# DPS_PWM-00.net
KiCad netlist of a schematic drawn in EAGLE
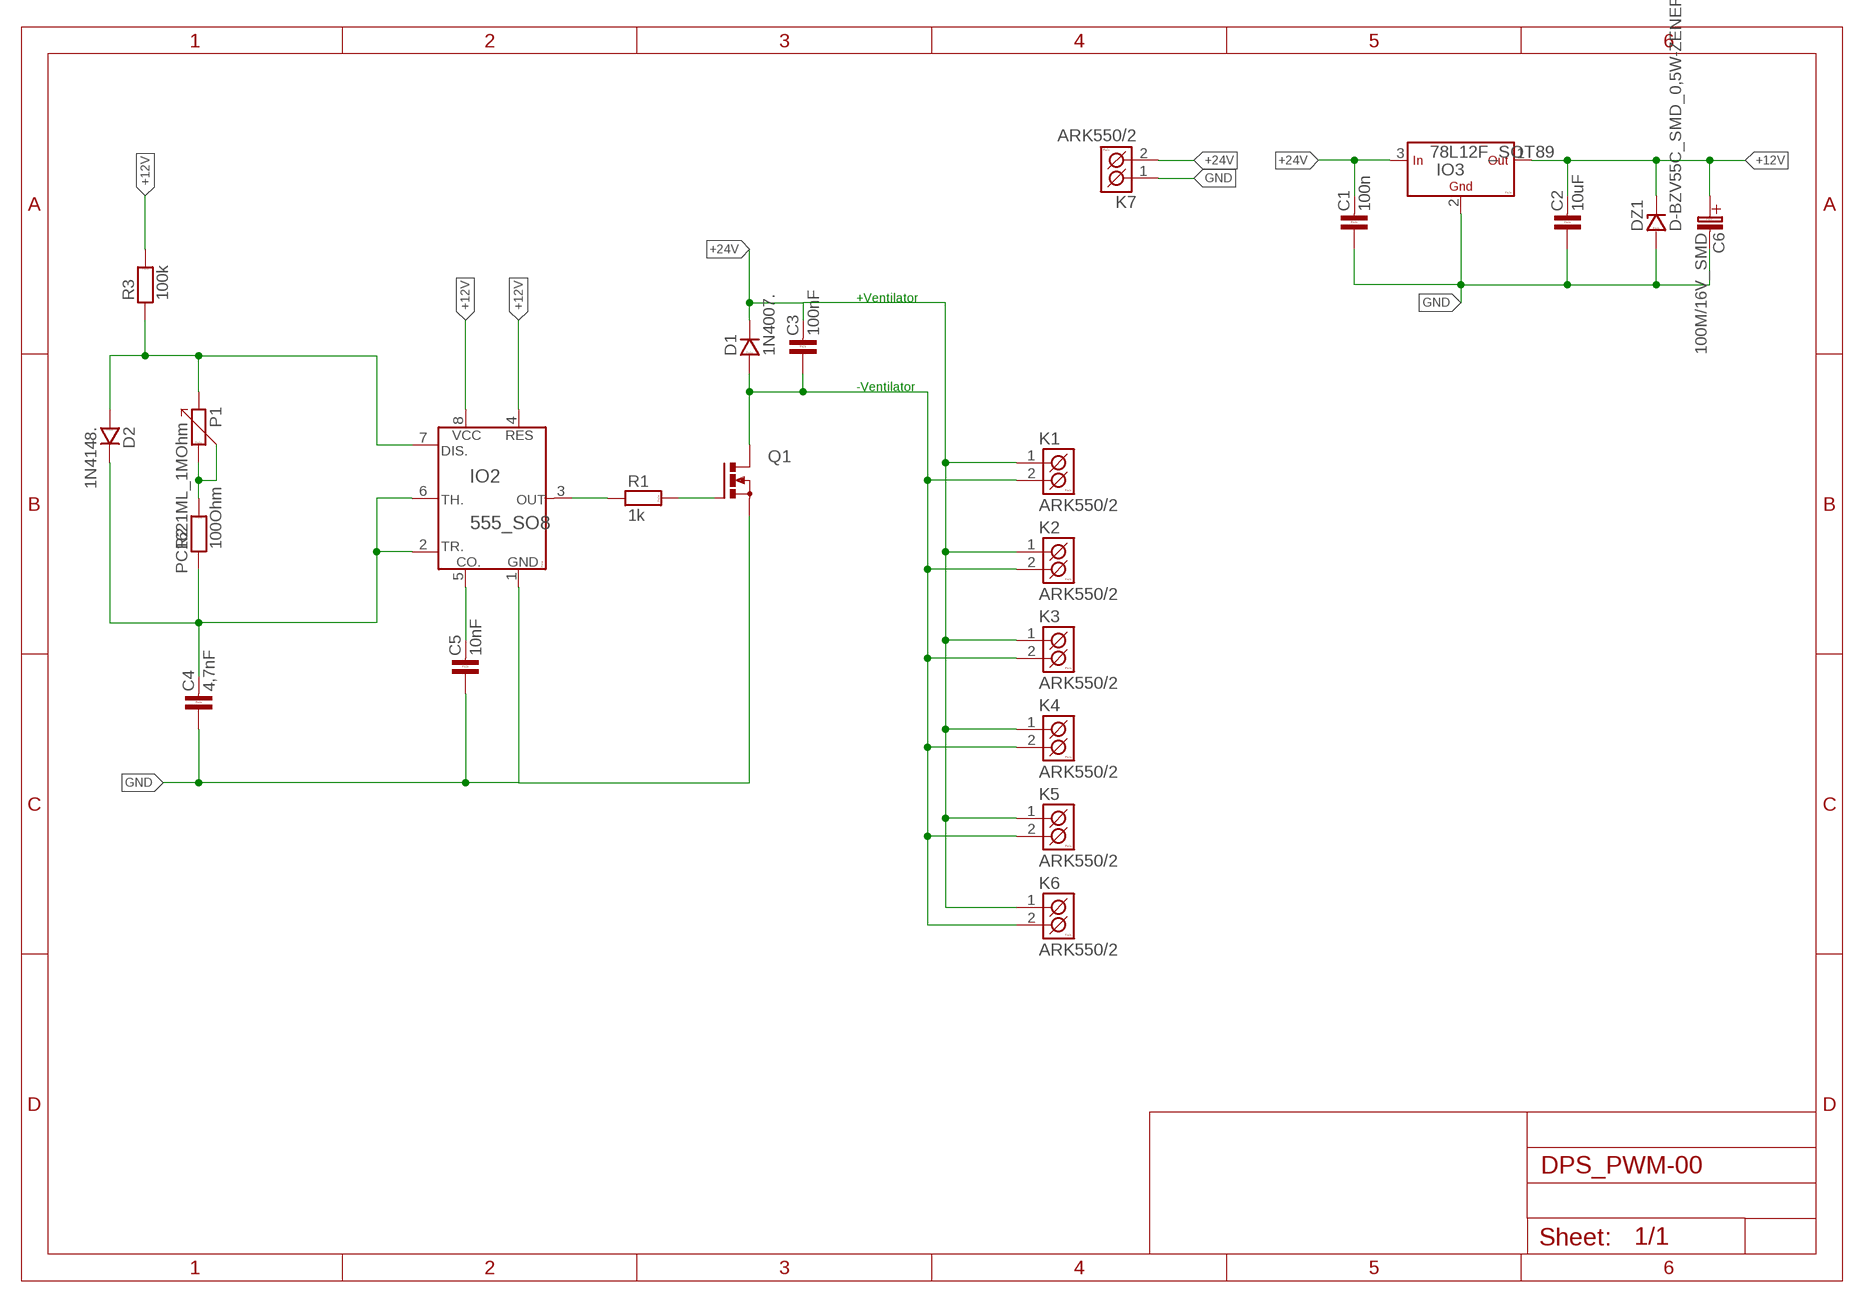
[diagram p0: schematic, sheet 1]

(export (version "E")
  (design (tool "Eeschema 10.0.6"))
  (components
    (comp (ref "C1")
      (value "100n")
      (footprint "eagle-import:1206")
      (libsource (lib "eagle-import") (part "C-KER_1206"))
    )
    (comp (ref "C2")
      (value "10uF")
      (footprint "eagle-import:1206")
      (libsource (lib "eagle-import") (part "C-KER_1206"))
    )
    (comp (ref "C3")
      (value "100nF")
      (footprint "eagle-import:1206")
      (libsource (lib "eagle-import") (part "C-KER_1206"))
    )
    (comp (ref "C4")
      (value "4,7nF")
      (footprint "eagle-import:1206")
      (libsource (lib "eagle-import") (part "C-KER_1206"))
    )
    (comp (ref "C5")
      (value "10nF")
      (footprint "eagle-import:1206")
      (libsource (lib "eagle-import") (part "C-KER_1206"))
    )
    (comp (ref "C6")
      (value "100M/16V_SMD")
      (footprint "eagle-import:C_EL-SMD_D")
      (libsource (lib "eagle-import") (part "100M/16V_SMD"))
    )
    (comp (ref "D1")
      (value "1N4007.")
      (footprint "eagle-import:SM-1")
      (libsource (lib "eagle-import") (part "1N4007."))
    )
    (comp (ref "D2")
      (value "1N4148.")
      (footprint "eagle-import:SOD-80")
      (libsource (lib "eagle-import") (part "1N4148."))
    )
    (comp (ref "DZ1")
      (value "D-BZV55C_SMD_0,5W-ZENER")
      (footprint "eagle-import:SOD-80")
      (libsource (lib "eagle-import") (part "D-?-ZENERBZV55C_SMD_0,5W"))
    )
    (comp (ref "IO2")
      (value "555_SO8")
      (footprint "eagle-import:SO08")
      (libsource (lib "eagle-import") (part "555_SO8"))
    )
    (comp (ref "IO3")
      (value "78L12F_SOT89")
      (footprint "eagle-import:SOT-89")
      (libsource (lib "eagle-import") (part "78?_SOT"))
    )
    (comp (ref "K1")
      (value "ARK550/2")
      (footprint "eagle-import:ARK550_2")
      (libsource (lib "eagle-import") (part "ARK550/2"))
    )
    (comp (ref "K2")
      (value "ARK550/2")
      (footprint "eagle-import:ARK550_2")
      (libsource (lib "eagle-import") (part "ARK550/2"))
    )
    (comp (ref "K3")
      (value "ARK550/2")
      (footprint "eagle-import:ARK550_2")
      (libsource (lib "eagle-import") (part "ARK550/2"))
    )
    (comp (ref "K4")
      (value "ARK550/2")
      (footprint "eagle-import:ARK550_2")
      (libsource (lib "eagle-import") (part "ARK550/2"))
    )
    (comp (ref "K5")
      (value "ARK550/2")
      (footprint "eagle-import:ARK550_2")
      (libsource (lib "eagle-import") (part "ARK550/2"))
    )
    (comp (ref "K6")
      (value "ARK550/2")
      (footprint "eagle-import:ARK550_2")
      (libsource (lib "eagle-import") (part "ARK550/2"))
    )
    (comp (ref "K7")
      (value "ARK550/2")
      (footprint "eagle-import:ARK550_2")
      (libsource (lib "eagle-import") (part "ARK550/2"))
    )
    (comp (ref "P1")
      (value "PC1621ML_1MOhm")
      (footprint "eagle-import:PC16ML")
      (libsource (lib "eagle-import") (part "PC16ML"))
    )
    (comp (ref "Q1")
      (value "PMOSFET_NTO220BH")
      (footprint "eagle-import:TO220BH")
      (libsource (lib "eagle-import") (part "PMOSFET_NTO220BH"))
    )
    (comp (ref "R1")
      (value "1k")
      (footprint "eagle-import:1206")
      (libsource (lib "eagle-import") (part "R_1206"))
    )
    (comp (ref "R2")
      (value "100Ohm")
      (footprint "eagle-import:1206")
      (libsource (lib "eagle-import") (part "R_1206"))
    )
    (comp (ref "R3")
      (value "100k")
      (footprint "eagle-import:1206")
      (libsource (lib "eagle-import") (part "R_1206"))
    )
  )
  (nets
    (net (code "1") (name "+12V") (class "Default")
      (node (ref "C2") (pin "2") (pinfunction "2_2") (pintype "passive"))
      (node (ref "C6") (pin "+") (pinfunction "C_EL+_+") (pintype "passive"))
      (node (ref "DZ1") (pin "K") (pinfunction "K_K") (pintype "passive"))
      (node (ref "IO2") (pin "4") (pinfunction "RES_4") (pintype "input"))
      (node (ref "IO2") (pin "8") (pinfunction "VCC_8") (pintype "power_in"))
      (node (ref "IO3") (pin "1") (pinfunction "OUT_1") (pintype "passive"))
      (node (ref "R3") (pin "2") (pinfunction "2_2") (pintype "passive"))
    )
    (net (code "2") (name "+24V") (class "Default")
      (node (ref "C1") (pin "2") (pinfunction "2_2") (pintype "passive"))
      (node (ref "C3") (pin "2") (pinfunction "2_2") (pintype "passive"))
      (node (ref "D1") (pin "K") (pinfunction "K_K") (pintype "passive"))
      (node (ref "IO3") (pin "3") (pinfunction "IN_3") (pintype "passive"))
      (node (ref "K1") (pin "1") (pinfunction "K1_1") (pintype "passive"))
      (node (ref "K2") (pin "1") (pinfunction "K1_1") (pintype "passive"))
      (node (ref "K3") (pin "1") (pinfunction "K1_1") (pintype "passive"))
      (node (ref "K4") (pin "1") (pinfunction "K1_1") (pintype "passive"))
      (node (ref "K5") (pin "1") (pinfunction "K1_1") (pintype "passive"))
      (node (ref "K6") (pin "1") (pinfunction "K1_1") (pintype "passive"))
      (node (ref "K7") (pin "2") (pinfunction "K2_2") (pintype "passive"))
    )
    (net (code "3") (name "GND") (class "Default")
      (node (ref "C1") (pin "1") (pinfunction "1_1") (pintype "passive"))
      (node (ref "C2") (pin "1") (pinfunction "1_1") (pintype "passive"))
      (node (ref "C4") (pin "1") (pinfunction "1_1") (pintype "passive"))
      (node (ref "C5") (pin "1") (pinfunction "1_1") (pintype "passive"))
      (node (ref "C6") (pin "-") (pinfunction "C_EL-_-") (pintype "passive"))
      (node (ref "DZ1") (pin "A") (pinfunction "A_A") (pintype "passive"))
      (node (ref "IO2") (pin "1") (pinfunction "GND_1") (pintype "power_in"))
      (node (ref "IO3") (pin "2") (pinfunction "GND_2") (pintype "passive"))
      (node (ref "K7") (pin "1") (pinfunction "K1_1") (pintype "passive"))
      (node (ref "Q1") (pin "S") (pinfunction "S_S") (pintype "passive"))
    )
    (net (code "4") (name "Net-(IO2-CO.)") (class "Default")
      (node (ref "C5") (pin "2") (pinfunction "2_2") (pintype "passive"))
      (node (ref "IO2") (pin "5") (pinfunction "CO._5") (pintype "input"))
    )
    (net (code "5") (name "Net-(IO2-DIS.)") (class "Default")
      (node (ref "D2") (pin "A") (pinfunction "A_A") (pintype "passive"))
      (node (ref "IO2") (pin "7") (pinfunction "DIS._7") (pintype "input"))
      (node (ref "P1") (pin "1") (pinfunction "1_1") (pintype "passive"))
      (node (ref "R3") (pin "1") (pinfunction "1_1") (pintype "passive"))
    )
    (net (code "6") (name "Net-(IO2-OUT)") (class "Default")
      (node (ref "IO2") (pin "3") (pinfunction "OUT_3") (pintype "output"))
      (node (ref "R1") (pin "1") (pinfunction "1_1") (pintype "passive"))
    )
    (net (code "7") (name "Net-(IO2-TH.)") (class "Default")
      (node (ref "C4") (pin "2") (pinfunction "2_2") (pintype "passive"))
      (node (ref "D2") (pin "K") (pinfunction "K_K") (pintype "passive"))
      (node (ref "IO2") (pin "2") (pinfunction "TR._2") (pintype "input"))
      (node (ref "IO2") (pin "6") (pinfunction "TH._6") (pintype "input"))
      (node (ref "R2") (pin "1") (pinfunction "1_1") (pintype "passive"))
    )
    (net (code "8") (name "Net-(K1-K2)") (class "Default")
      (node (ref "C3") (pin "1") (pinfunction "1_1") (pintype "passive"))
      (node (ref "D1") (pin "A") (pinfunction "A_A") (pintype "passive"))
      (node (ref "K1") (pin "2") (pinfunction "K2_2") (pintype "passive"))
      (node (ref "K2") (pin "2") (pinfunction "K2_2") (pintype "passive"))
      (node (ref "K3") (pin "2") (pinfunction "K2_2") (pintype "passive"))
      (node (ref "K4") (pin "2") (pinfunction "K2_2") (pintype "passive"))
      (node (ref "K5") (pin "2") (pinfunction "K2_2") (pintype "passive"))
      (node (ref "K6") (pin "2") (pinfunction "K2_2") (pintype "passive"))
      (node (ref "Q1") (pin "D") (pinfunction "D_D") (pintype "passive"))
    )
    (net (code "9") (name "Net-(P1-Pad2)") (class "Default")
      (node (ref "P1") (pin "2") (pinfunction "2_2") (pintype "passive"))
      (node (ref "P1") (pin "3") (pinfunction "3_3") (pintype "passive"))
      (node (ref "R2") (pin "2") (pinfunction "2_2") (pintype "passive"))
    )
    (net (code "10") (name "Net-(Q1-PadG)") (class "Default")
      (node (ref "Q1") (pin "G") (pinfunction "G_G") (pintype "passive"))
      (node (ref "R1") (pin "2") (pinfunction "2_2") (pintype "passive"))
    )
  )
)
